# Debouncer.net
KiCad netlist of a schematic drawn in EAGLE
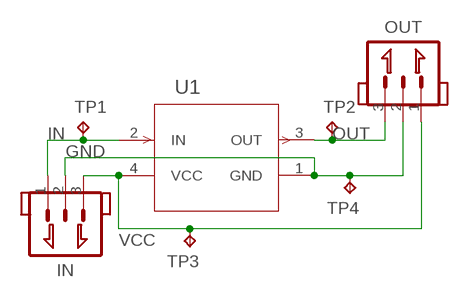
[diagram p0: schematic, sheet 1]

(export (version "E")
  (design (tool "Eeschema 10.0.6"))
  (components
    (comp (ref "IN")
      (value "JST_1.25_3P")
      (footprint "eagle-import:JST1.25_3P")
      (libsource (lib "eagle-import") (part "JST_1.25_3P"))
    )
    (comp (ref "OUT")
      (value "JST_1.25_3P")
      (footprint "eagle-import:JST1.25_3P")
      (libsource (lib "eagle-import") (part "JST_1.25_3P"))
    )
    (comp (ref "TP1")
      (value "TPPAD1-13")
      (footprint "eagle-import:P1-13")
      (libsource (lib "eagle-import") (part "TPPAD1-13"))
    )
    (comp (ref "TP2")
      (value "TPPAD1-13")
      (footprint "eagle-import:P1-13")
      (libsource (lib "eagle-import") (part "TPPAD1-13"))
    )
    (comp (ref "TP3")
      (value "TPPAD1-13")
      (footprint "eagle-import:P1-13")
      (libsource (lib "eagle-import") (part "TPPAD1-13"))
    )
    (comp (ref "TP4")
      (value "TPPAD1-13")
      (footprint "eagle-import:P1-13")
      (libsource (lib "eagle-import") (part "TPPAD1-13"))
    )
    (comp (ref "U1")
      (value "DEBOUNCE_MAX6816EUS+T")
      (footprint "eagle-import:21-0052F")
      (fields (field (name "MANUFACTURER_PART_NUMBER") "MAX6816EUS+T"))
      (libsource (lib "eagle-import") (part "DEBOUNCE_MAX6816EUS+T"))
    )
  )
  (nets
    (net (code "1") (name "/GND") (class "Default")
      (node (ref "IN") (pin "2") (pinfunction "2_2") (pintype "passive"))
      (node (ref "OUT") (pin "2") (pinfunction "2_2") (pintype "passive"))
      (node (ref "TP4") (pin "TP") (pinfunction "TP_TP") (pintype "input"))
      (node (ref "U1") (pin "1") (pinfunction "GND_1") (pintype "power_in"))
    )
    (net (code "2") (name "/IN") (class "Default")
      (node (ref "IN") (pin "1") (pinfunction "1_1") (pintype "passive"))
      (node (ref "TP1") (pin "TP") (pinfunction "TP_TP") (pintype "input"))
      (node (ref "U1") (pin "2") (pinfunction "IN_2") (pintype "input"))
    )
    (net (code "3") (name "/OUT") (class "Default")
      (node (ref "OUT") (pin "3") (pinfunction "3_3") (pintype "passive"))
      (node (ref "TP2") (pin "TP") (pinfunction "TP_TP") (pintype "input"))
      (node (ref "U1") (pin "3") (pinfunction "OUT_3") (pintype "output"))
    )
    (net (code "4") (name "/VCC") (class "Default")
      (node (ref "IN") (pin "3") (pinfunction "3_3") (pintype "passive"))
      (node (ref "OUT") (pin "1") (pinfunction "1_1") (pintype "passive"))
      (node (ref "TP3") (pin "TP") (pinfunction "TP_TP") (pintype "input"))
      (node (ref "U1") (pin "4") (pinfunction "VCC_4") (pintype "power_in"))
    )
  )
)
